# Shut_Down_Signal_Control.net
KiCad netlist of a schematic drawn in Altium Designer
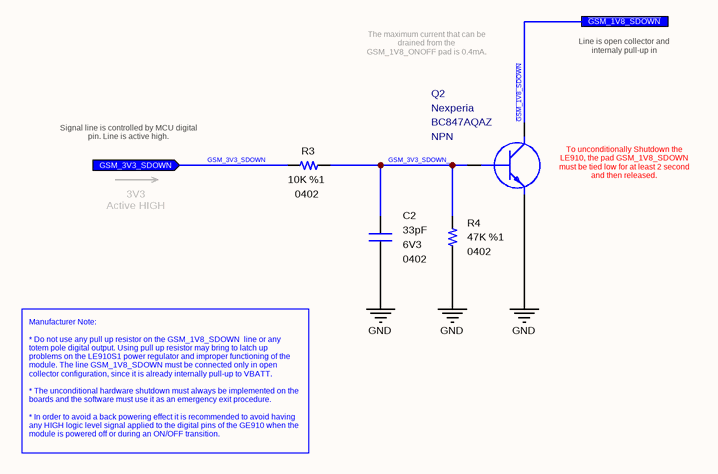
[diagram p0: Shut Down Signal Control.SchDoc]

(export (version "E")
  (design (tool "Eeschema 10.0.6"))
  (components
    (comp (ref "C2")
      (value "33pF")
      (footprint "CAPACITOR_0402")
      (description "Capacitor - 33pF [0402] (Ceramic)")
      (fields
        (field (name "CASE") "0402")
        (field (name "VOLTAGE") "6V3")
        (field (name "MANUFACTURER PART NUMBER") "C0402C330J9RACAUTO")
        (field (name "TOLERANCE") "10%")
      )
      (libsource (lib "P101DA_Library") (part "33pF [0402-6V3]"))
    )
    (comp (ref "Q2")
      (value "~")
      (footprint "SOT1215")
      (description "Bipolar NPN Transistors")
      (fields
        (field (name "POLARITY") "NPN")
        (field (name "MANUFACTURER PART NUMBER") "BC847AQAZ")
        (field (name "MANUFACTURER NAME") "Nexperia")
      )
      (libsource (lib "P101DA_Library") (part "BC847"))
    )
    (comp (ref "R3")
      (value "10K")
      (footprint "RESISTOR_0402")
      (description "Thick Film Resistors - SMD 1/16 W 10 Kohms 1%")
      (fields
        (field (name "CASE") "0402")
        (field (name "MANUFACTURER PART NUMBER") "CRCW040210K0FKED")
        (field (name "TOLERANCE") "%1")
      )
      (libsource (lib "P101DA_Library") (part "10K"))
    )
    (comp (ref "R4")
      (value "47K")
      (footprint "RESISTOR_0402")
      (description "Thick Film Resistors - SMD 1/16 W 47 Kohms 1%")
      (fields
        (field (name "CASE") "0402")
        (field (name "MANUFACTURER PART NUMBER") "CRCW040247K0FKED")
        (field (name "TOLERANCE") "%1")
      )
      (libsource (lib "P101DA_Library") (part "47K"))
    )
  )
  (nets
    (net (code "1") (name "/GSM_3V3_SDOWN") (class "Default")
      (node (ref "R3") (pin "2") (pinfunction "2_2") (pintype "passive"))
    )
    (net (code "2") (name "/GSM_3V3_SDOWN_") (class "Default")
      (node (ref "C2") (pin "2") (pinfunction "2_2") (pintype "passive"))
      (node (ref "Q2") (pin "1") (pinfunction "B_1") (pintype "passive"))
      (node (ref "R3") (pin "1") (pinfunction "1_1") (pintype "passive"))
      (node (ref "R4") (pin "2") (pinfunction "2_2") (pintype "passive"))
    )
    (net (code "3") (name "/~{GSM_1V8_SDOWN}") (class "Default")
      (node (ref "Q2") (pin "3") (pinfunction "C_3") (pintype "passive"))
    )
    (net (code "4") (name "GND") (class "Default")
      (node (ref "C2") (pin "1") (pinfunction "1_1") (pintype "passive"))
      (node (ref "Q2") (pin "2") (pinfunction "E_2") (pintype "passive"))
      (node (ref "R4") (pin "1") (pinfunction "1_1") (pintype "passive"))
    )
  )
)
